# ModuleCarrier-Laird-BL652-v1_0_0.net
KiCad netlist of a schematic drawn in EAGLE
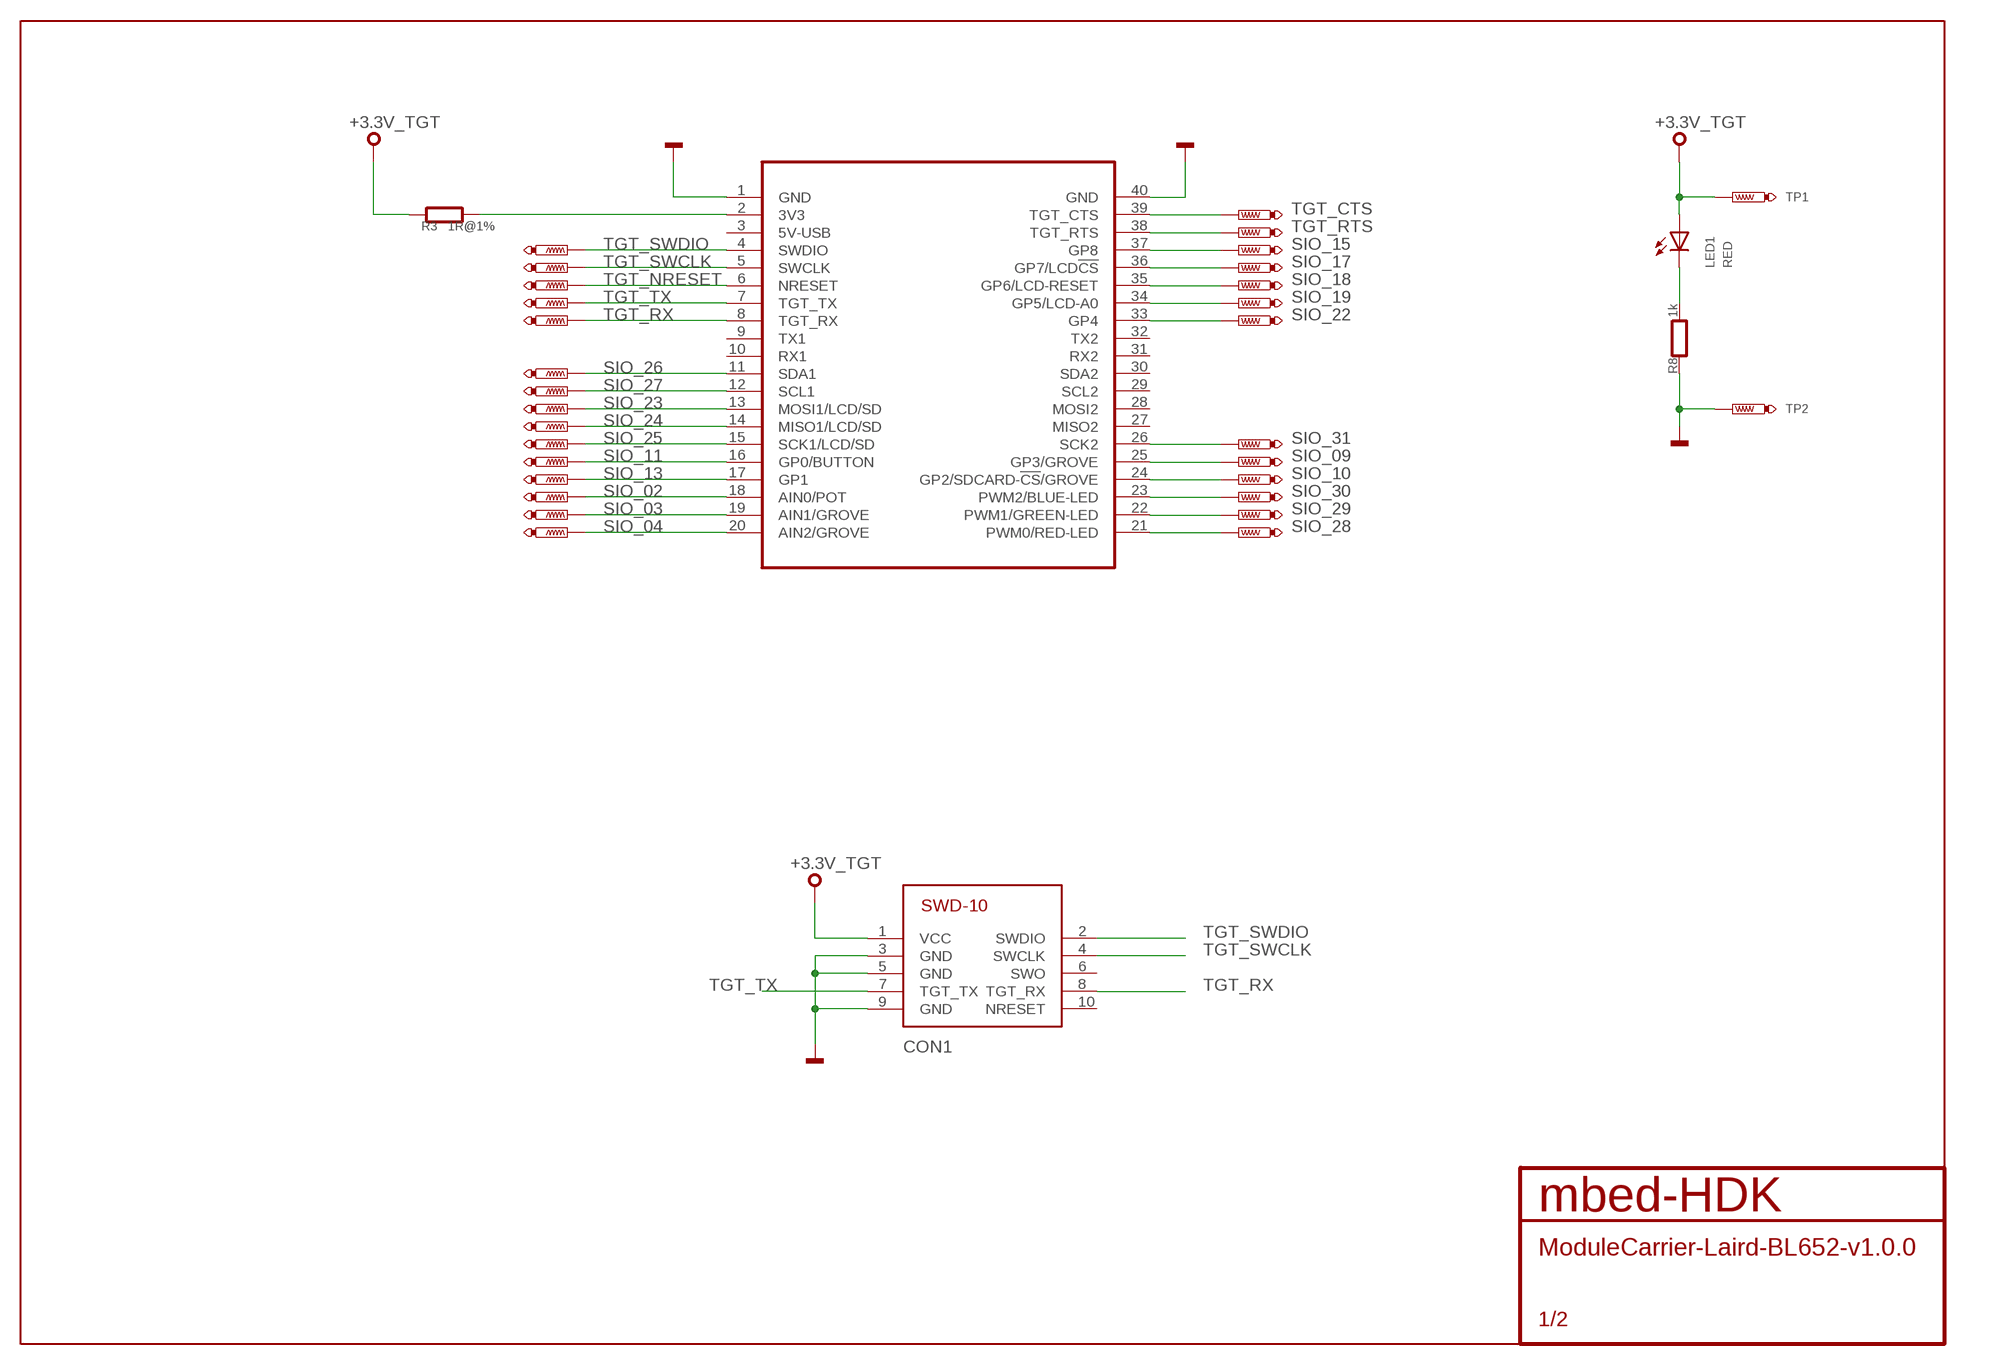
[diagram p0: schematic, sheet 1]
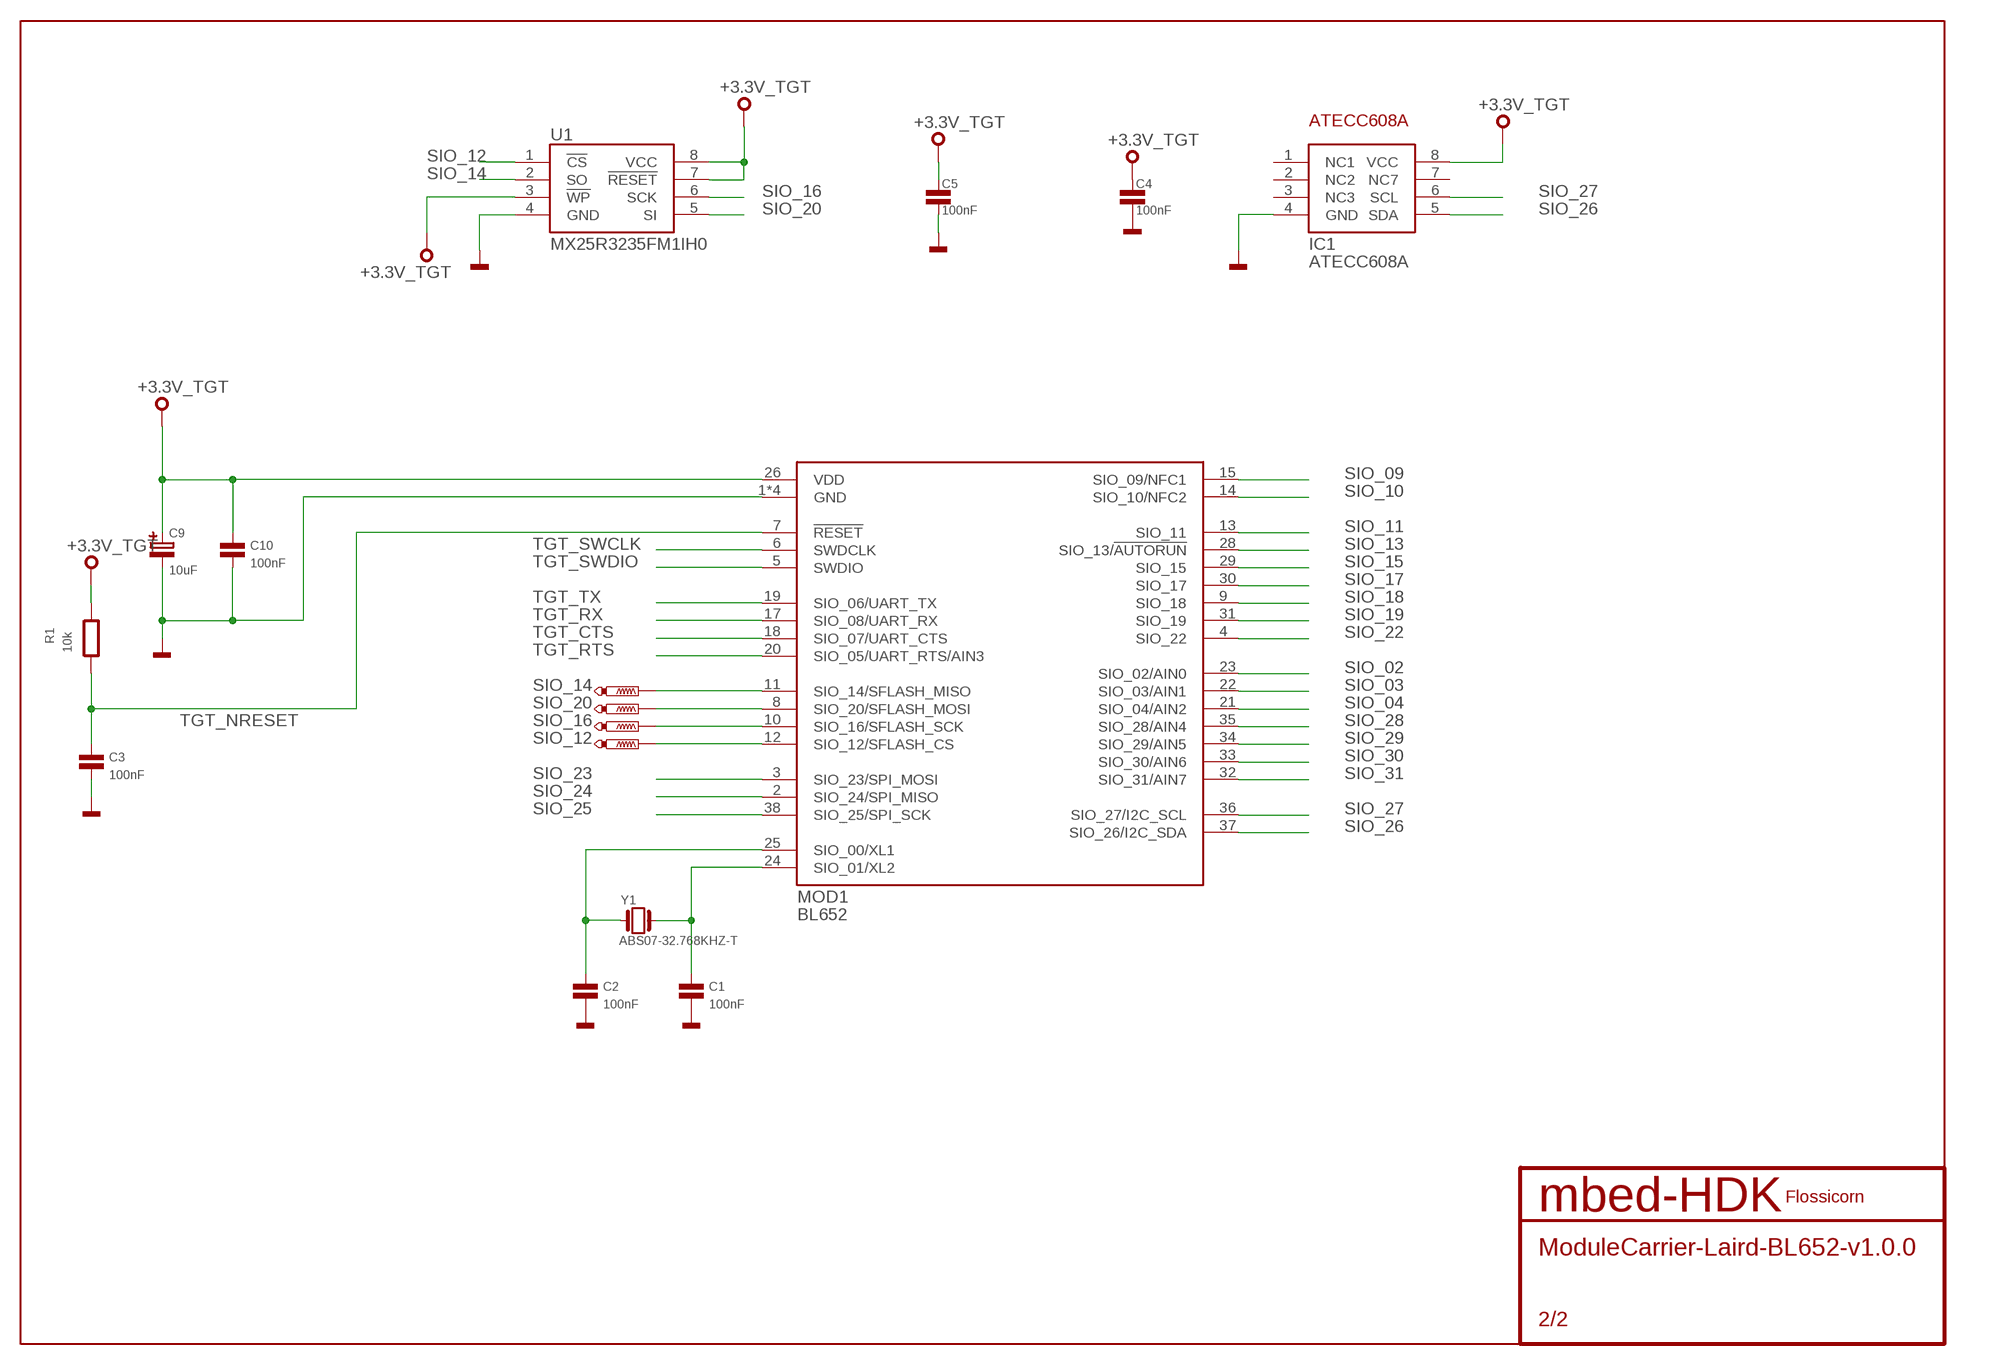
[diagram p1: schematic, sheet 2]

(export (version "E")
  (design (tool "Eeschema 10.0.6"))
  (components
    (comp (ref "C1")
      (value "100nF")
      (footprint "eagle-import:0603")
      (libsource (lib "eagle-import") (part "C0603"))
    )
    (comp (ref "C2")
      (value "100nF")
      (footprint "eagle-import:0603")
      (libsource (lib "eagle-import") (part "C0603"))
    )
    (comp (ref "C3")
      (value "100nF")
      (footprint "eagle-import:0603")
      (libsource (lib "eagle-import") (part "C0603"))
    )
    (comp (ref "C4")
      (value "100nF")
      (footprint "eagle-import:0603")
      (libsource (lib "eagle-import") (part "CAPACITOR0603"))
    )
    (comp (ref "C5")
      (value "100nF")
      (footprint "eagle-import:0603")
      (libsource (lib "eagle-import") (part "CAPACITOR0603"))
    )
    (comp (ref "C9")
      (value "10uF")
      (footprint "eagle-import:SMC_B")
      (fields (field (name "MF") "Kemet"))
      (libsource (lib "eagle-import") (part "CAPACITOR-POLARISEDB"))
    )
    (comp (ref "C10")
      (value "100nF")
      (footprint "eagle-import:0603")
      (libsource (lib "eagle-import") (part "C0603"))
    )
    (comp (ref "IC1")
      (value "ATECC608A")
      (footprint "eagle-import:SO8")
      (libsource (lib "eagle-import") (part "ATECC608A"))
    )
    (comp (ref "MOD1")
      (value "BL652")
      (footprint "eagle-import:BL652")
      (libsource (lib "eagle-import") (part "BL652"))
    )
    (comp (ref "R1")
      (value "10k")
      (footprint "eagle-import:0603")
      (libsource (lib "eagle-import") (part "RESISTOR0603"))
    )
    (comp (ref "SS1")
      (value "FLOSSICORN0.25")
      (footprint "eagle-import:FLOSSICORN-0.25")
      (libsource (lib "eagle-import") (part "FLOSSICORN0.25"))
    )
    (comp (ref "TP31")
      (value "PTR1TP07R")
      (footprint "eagle-import:TP07R")
      (libsource (lib "eagle-import") (part "PTR1TP07R"))
    )
    (comp (ref "TP32")
      (value "PTR1TP07R")
      (footprint "eagle-import:TP07R")
      (libsource (lib "eagle-import") (part "PTR1TP07R"))
    )
    (comp (ref "TP33")
      (value "PTR1TP07R")
      (footprint "eagle-import:TP07R")
      (libsource (lib "eagle-import") (part "PTR1TP07R"))
    )
    (comp (ref "TP34")
      (value "PTR1TP07R")
      (footprint "eagle-import:TP07R")
      (libsource (lib "eagle-import") (part "PTR1TP07R"))
    )
    (comp (ref "U1")
      (value "MX25R3235FM1IH0")
      (footprint "eagle-import:SO8")
      (fields (field (name "MF") "Macronix"))
      (libsource (lib "eagle-import") (part "MX25R3235FM1IH0"))
    )
    (comp (ref "Y1")
      (value "ABS07-32.768KHZ-T")
      (footprint "eagle-import:FC135")
      (fields (field (name "MF") "Abracon"))
      (libsource (lib "eagle-import") (part "ABS07-32.768KHZ-T"))
    )
    (comp (ref "CON1")
      (value "SWD-10/TC2050_SMD")
      (footprint "eagle-import:FTSH-105-02")
      (libsource (lib "eagle-import") (part "SWD-10/TC2050_SMD"))
    )
    (comp (ref "LED1")
      (value "RED")
      (footprint "eagle-import:CHIPLED_0603")
      (fields (field (name "MF") "Wurth Electronics Inc"))
      (libsource (lib "eagle-import") (part "SMD_LED0603"))
    )
    (comp (ref "MOD2")
      (value "MODULE_DAUGHTER")
      (footprint "eagle-import:MODULE_DAUGHTER")
      (libsource (lib "eagle-import") (part "MODULE_DAUGHTER"))
    )
    (comp (ref "R3")
      (value "1R@1%")
      (footprint "eagle-import:0603")
      (libsource (lib "eagle-import") (part "RESISTOR0603"))
    )
    (comp (ref "R8")
      (value "1k")
      (footprint "eagle-import:0603")
      (libsource (lib "eagle-import") (part "RESISTOR0603"))
    )
    (comp (ref "TP1")
      (value "TEST-POINT-50R-PTH")
      (footprint "eagle-import:TP50-PTH")
      (libsource (lib "eagle-import") (part "TEST-POINT-50R-PTH"))
    )
    (comp (ref "TP2")
      (value "TEST-POINT-50R-PTH")
      (footprint "eagle-import:TP50-PTH")
      (libsource (lib "eagle-import") (part "TEST-POINT-50R-PTH"))
    )
    (comp (ref "TP3")
      (value "PTR1TP07R")
      (footprint "eagle-import:TP07R")
      (libsource (lib "eagle-import") (part "PTR1TP07R"))
    )
    (comp (ref "TP4")
      (value "PTR1TP07R")
      (footprint "eagle-import:TP07R")
      (libsource (lib "eagle-import") (part "PTR1TP07R"))
    )
    (comp (ref "TP5")
      (value "PTR1TP07R")
      (footprint "eagle-import:TP07R")
      (libsource (lib "eagle-import") (part "PTR1TP07R"))
    )
    (comp (ref "TP6")
      (value "PTR1TP07R")
      (footprint "eagle-import:TP07R")
      (libsource (lib "eagle-import") (part "PTR1TP07R"))
    )
    (comp (ref "TP7")
      (value "PTR1TP07R")
      (footprint "eagle-import:TP07R")
      (libsource (lib "eagle-import") (part "PTR1TP07R"))
    )
    (comp (ref "TP8")
      (value "PTR1TP07R")
      (footprint "eagle-import:TP07R")
      (libsource (lib "eagle-import") (part "PTR1TP07R"))
    )
    (comp (ref "TP9")
      (value "PTR1TP07R")
      (footprint "eagle-import:TP07R")
      (libsource (lib "eagle-import") (part "PTR1TP07R"))
    )
    (comp (ref "TP10")
      (value "PTR1TP07R")
      (footprint "eagle-import:TP07R")
      (libsource (lib "eagle-import") (part "PTR1TP07R"))
    )
    (comp (ref "TP11")
      (value "PTR1TP07R")
      (footprint "eagle-import:TP07R")
      (libsource (lib "eagle-import") (part "PTR1TP07R"))
    )
    (comp (ref "TP12")
      (value "PTR1TP07R")
      (footprint "eagle-import:TP07R")
      (libsource (lib "eagle-import") (part "PTR1TP07R"))
    )
    (comp (ref "TP13")
      (value "PTR1TP07R")
      (footprint "eagle-import:TP07R")
      (libsource (lib "eagle-import") (part "PTR1TP07R"))
    )
    (comp (ref "TP14")
      (value "PTR1TP07R")
      (footprint "eagle-import:TP07R")
      (libsource (lib "eagle-import") (part "PTR1TP07R"))
    )
    (comp (ref "TP15")
      (value "PTR1TP07R")
      (footprint "eagle-import:TP07R")
      (libsource (lib "eagle-import") (part "PTR1TP07R"))
    )
    (comp (ref "TP16")
      (value "PTR1TP07R")
      (footprint "eagle-import:TP07R")
      (libsource (lib "eagle-import") (part "PTR1TP07R"))
    )
    (comp (ref "TP17")
      (value "PTR1TP07R")
      (footprint "eagle-import:TP07R")
      (libsource (lib "eagle-import") (part "PTR1TP07R"))
    )
    (comp (ref "TP18")
      (value "PTR1TP07R")
      (footprint "eagle-import:TP07R")
      (libsource (lib "eagle-import") (part "PTR1TP07R"))
    )
    (comp (ref "TP19")
      (value "PTR1TP07R")
      (footprint "eagle-import:TP07R")
      (libsource (lib "eagle-import") (part "PTR1TP07R"))
    )
    (comp (ref "TP20")
      (value "PTR1TP07R")
      (footprint "eagle-import:TP07R")
      (libsource (lib "eagle-import") (part "PTR1TP07R"))
    )
    (comp (ref "TP21")
      (value "PTR1TP07R")
      (footprint "eagle-import:TP07R")
      (libsource (lib "eagle-import") (part "PTR1TP07R"))
    )
    (comp (ref "TP22")
      (value "PTR1TP07R")
      (footprint "eagle-import:TP07R")
      (libsource (lib "eagle-import") (part "PTR1TP07R"))
    )
    (comp (ref "TP23")
      (value "PTR1TP07R")
      (footprint "eagle-import:TP07R")
      (libsource (lib "eagle-import") (part "PTR1TP07R"))
    )
    (comp (ref "TP24")
      (value "PTR1TP07R")
      (footprint "eagle-import:TP07R")
      (libsource (lib "eagle-import") (part "PTR1TP07R"))
    )
    (comp (ref "TP25")
      (value "PTR1TP07R")
      (footprint "eagle-import:TP07R")
      (libsource (lib "eagle-import") (part "PTR1TP07R"))
    )
    (comp (ref "TP26")
      (value "PTR1TP07R")
      (footprint "eagle-import:TP07R")
      (libsource (lib "eagle-import") (part "PTR1TP07R"))
    )
    (comp (ref "TP27")
      (value "PTR1TP07R")
      (footprint "eagle-import:TP07R")
      (libsource (lib "eagle-import") (part "PTR1TP07R"))
    )
    (comp (ref "TP28")
      (value "PTR1TP07R")
      (footprint "eagle-import:TP07R")
      (libsource (lib "eagle-import") (part "PTR1TP07R"))
    )
    (comp (ref "TP29")
      (value "PTR1TP07R")
      (footprint "eagle-import:TP07R")
      (libsource (lib "eagle-import") (part "PTR1TP07R"))
    )
    (comp (ref "TP30")
      (value "PTR1TP07R")
      (footprint "eagle-import:TP07R")
      (libsource (lib "eagle-import") (part "PTR1TP07R"))
    )
  )
  (nets
    (net (code "1") (name "+3.3V_TGT") (class "Default")
      (node (ref "C10") (pin "1") (pinfunction "P$1_1") (pintype "passive"))
      (node (ref "C4") (pin "1") (pinfunction "P$1_1") (pintype "passive"))
      (node (ref "C5") (pin "1") (pinfunction "P$1_1") (pintype "passive"))
      (node (ref "C9") (pin "+") (pinfunction "+_+") (pintype "passive"))
      (node (ref "CON1") (pin "1") (pinfunction "VCC_1") (pintype "bidirectional"))
      (node (ref "IC1") (pin "8") (pinfunction "VCC_8") (pintype "bidirectional"))
      (node (ref "LED1") (pin "A") (pinfunction "A_A") (pintype "passive"))
      (node (ref "MOD1") (pin "26") (pinfunction "VDD_26") (pintype "bidirectional"))
      (node (ref "R1") (pin "2") (pinfunction "P$2_2") (pintype "passive"))
      (node (ref "R3") (pin "1") (pinfunction "P$1_1") (pintype "passive"))
      (node (ref "TP1") (pin "TP") (pinfunction "TP_TP") (pintype "input"))
      (node (ref "U1") (pin "3") (pinfunction "~{WP}_3") (pintype "bidirectional"))
      (node (ref "U1") (pin "7") (pinfunction "~{RESET}_7") (pintype "bidirectional"))
      (node (ref "U1") (pin "8") (pinfunction "VCC_8") (pintype "bidirectional"))
    )
    (net (code "2") (name "GND") (class "Default")
      (node (ref "C1") (pin "2") (pinfunction "P$2_2") (pintype "passive"))
      (node (ref "C10") (pin "2") (pinfunction "P$2_2") (pintype "passive"))
      (node (ref "C2") (pin "2") (pinfunction "P$2_2") (pintype "passive"))
      (node (ref "C3") (pin "2") (pinfunction "P$2_2") (pintype "passive"))
      (node (ref "C4") (pin "2") (pinfunction "P$2_2") (pintype "passive"))
      (node (ref "C5") (pin "2") (pinfunction "P$2_2") (pintype "passive"))
      (node (ref "C9") (pin "-") (pinfunction "-_-") (pintype "passive"))
      (node (ref "CON1") (pin "3") (pinfunction "GND_3") (pintype "bidirectional"))
      (node (ref "CON1") (pin "5") (pinfunction "GND_5") (pintype "bidirectional"))
      (node (ref "CON1") (pin "9") (pinfunction "GND_9") (pintype "bidirectional"))
      (node (ref "IC1") (pin "4") (pinfunction "GND_4") (pintype "bidirectional"))
      (node (ref "MOD1") (pin "1") (pinfunction "GND_1") (pintype "bidirectional"))
      (node (ref "MOD1") (pin "16") (pinfunction "GND_16") (pintype "bidirectional"))
      (node (ref "MOD1") (pin "27") (pinfunction "GND_27") (pintype "bidirectional"))
      (node (ref "MOD1") (pin "39") (pinfunction "GND_39") (pintype "bidirectional"))
      (node (ref "MOD2") (pin "1") (pinfunction "GND_1") (pintype "bidirectional"))
      (node (ref "MOD2") (pin "40") (pinfunction "GND_40") (pintype "bidirectional"))
      (node (ref "R8") (pin "1") (pinfunction "P$1_1") (pintype "passive"))
      (node (ref "TP2") (pin "TP") (pinfunction "TP_TP") (pintype "input"))
      (node (ref "U1") (pin "4") (pinfunction "GND_4") (pintype "bidirectional"))
    )
    (net (code "3") (name "Net-(C1-P$1)") (class "Default")
      (node (ref "C1") (pin "1") (pinfunction "P$1_1") (pintype "passive"))
      (node (ref "MOD1") (pin "24") (pinfunction "SIO_01/XL2_24") (pintype "bidirectional"))
      (node (ref "Y1") (pin "X2") (pinfunction "2_X2") (pintype "passive"))
    )
    (net (code "4") (name "Net-(C2-P$1)") (class "Default")
      (node (ref "C2") (pin "1") (pinfunction "P$1_1") (pintype "passive"))
      (node (ref "MOD1") (pin "25") (pinfunction "SIO_00/XL1_25") (pintype "bidirectional"))
      (node (ref "Y1") (pin "X1") (pinfunction "1_X1") (pintype "passive"))
    )
    (net (code "5") (name "Net-(MOD2-3V3)") (class "Default")
      (node (ref "MOD2") (pin "2") (pinfunction "3V3_2") (pintype "bidirectional"))
      (node (ref "R3") (pin "2") (pinfunction "P$2_2") (pintype "passive"))
    )
    (net (code "6") (name "Net-(R8-P$2)") (class "Default")
      (node (ref "LED1") (pin "C") (pinfunction "C_C") (pintype "passive"))
      (node (ref "R8") (pin "2") (pinfunction "P$2_2") (pintype "passive"))
    )
    (net (code "7") (name "SIO_02") (class "Default")
      (node (ref "MOD1") (pin "23") (pinfunction "SIO_02/AIN0_23") (pintype "bidirectional"))
      (node (ref "MOD2") (pin "18") (pinfunction "AIN0/POT_18") (pintype "bidirectional"))
      (node (ref "TP10") (pin "TP") (pinfunction "TP_TP") (pintype "input"))
    )
    (net (code "8") (name "SIO_03") (class "Default")
      (node (ref "MOD1") (pin "22") (pinfunction "SIO_03/AIN1_22") (pintype "bidirectional"))
      (node (ref "MOD2") (pin "19") (pinfunction "AIN1/GROVE_19") (pintype "bidirectional"))
      (node (ref "TP11") (pin "TP") (pinfunction "TP_TP") (pintype "input"))
    )
    (net (code "9") (name "SIO_04") (class "Default")
      (node (ref "MOD1") (pin "21") (pinfunction "SIO_04/AIN2_21") (pintype "bidirectional"))
      (node (ref "MOD2") (pin "20") (pinfunction "AIN2/GROVE_20") (pintype "bidirectional"))
      (node (ref "TP12") (pin "TP") (pinfunction "TP_TP") (pintype "input"))
    )
    (net (code "10") (name "SIO_09") (class "Default")
      (node (ref "MOD1") (pin "15") (pinfunction "SIO_09/NFC1_15") (pintype "bidirectional"))
      (node (ref "MOD2") (pin "25") (pinfunction "GP3/GROVE_25") (pintype "bidirectional"))
      (node (ref "TP17") (pin "TP") (pinfunction "TP_TP") (pintype "input"))
    )
    (net (code "11") (name "SIO_10") (class "Default")
      (node (ref "MOD1") (pin "14") (pinfunction "SIO_10/NFC2_14") (pintype "bidirectional"))
      (node (ref "MOD2") (pin "24") (pinfunction "GP2/SDCARD-~{CS}/GROVE_24") (pintype "bidirectional"))
      (node (ref "TP16") (pin "TP") (pinfunction "TP_TP") (pintype "input"))
    )
    (net (code "12") (name "SIO_11") (class "Default")
      (node (ref "MOD1") (pin "13") (pinfunction "SIO_11_13") (pintype "bidirectional"))
      (node (ref "MOD2") (pin "16") (pinfunction "GP0/BUTTON_16") (pintype "bidirectional"))
      (node (ref "TP8") (pin "TP") (pinfunction "TP_TP") (pintype "input"))
    )
    (net (code "13") (name "SIO_12") (class "Default")
      (node (ref "MOD1") (pin "12") (pinfunction "SIO_12/SFLASH_CS_12") (pintype "bidirectional"))
      (node (ref "TP34") (pin "TP") (pinfunction "TP_TP") (pintype "input"))
      (node (ref "U1") (pin "1") (pinfunction "~{CS}_1") (pintype "bidirectional"))
    )
    (net (code "14") (name "SIO_13") (class "Default")
      (node (ref "MOD1") (pin "28") (pinfunction "SIO_13/~{AUTORUN}_28") (pintype "bidirectional"))
      (node (ref "MOD2") (pin "17") (pinfunction "GP1_17") (pintype "bidirectional"))
      (node (ref "TP9") (pin "TP") (pinfunction "TP_TP") (pintype "input"))
    )
    (net (code "15") (name "SIO_14") (class "Default")
      (node (ref "MOD1") (pin "11") (pinfunction "SIO_14/SFLASH_MISO_11") (pintype "bidirectional"))
      (node (ref "TP31") (pin "TP") (pinfunction "TP_TP") (pintype "input"))
      (node (ref "U1") (pin "2") (pinfunction "SO_2") (pintype "bidirectional"))
    )
    (net (code "16") (name "SIO_15") (class "Default")
      (node (ref "MOD1") (pin "29") (pinfunction "SIO_15_29") (pintype "bidirectional"))
      (node (ref "MOD2") (pin "37") (pinfunction "GP8_37") (pintype "bidirectional"))
      (node (ref "TP22") (pin "TP") (pinfunction "TP_TP") (pintype "input"))
    )
    (net (code "17") (name "SIO_16") (class "Default")
      (node (ref "MOD1") (pin "10") (pinfunction "SIO_16/SFLASH_SCK_10") (pintype "bidirectional"))
      (node (ref "TP33") (pin "TP") (pinfunction "TP_TP") (pintype "input"))
      (node (ref "U1") (pin "6") (pinfunction "SCK_6") (pintype "bidirectional"))
    )
    (net (code "18") (name "SIO_17") (class "Default")
      (node (ref "MOD1") (pin "30") (pinfunction "SIO_17_30") (pintype "bidirectional"))
      (node (ref "MOD2") (pin "36") (pinfunction "GP7/LCD~{CS}_36") (pintype "bidirectional"))
      (node (ref "TP21") (pin "TP") (pinfunction "TP_TP") (pintype "input"))
    )
    (net (code "19") (name "SIO_18") (class "Default")
      (node (ref "MOD1") (pin "9") (pinfunction "SIO_18_9") (pintype "bidirectional"))
      (node (ref "MOD2") (pin "35") (pinfunction "GP6/LCD-RESET_35") (pintype "bidirectional"))
      (node (ref "TP20") (pin "TP") (pinfunction "TP_TP") (pintype "input"))
    )
    (net (code "20") (name "SIO_19") (class "Default")
      (node (ref "MOD1") (pin "31") (pinfunction "SIO_19_31") (pintype "bidirectional"))
      (node (ref "MOD2") (pin "34") (pinfunction "GP5/LCD-A0_34") (pintype "bidirectional"))
      (node (ref "TP19") (pin "TP") (pinfunction "TP_TP") (pintype "input"))
    )
    (net (code "21") (name "SIO_20") (class "Default")
      (node (ref "MOD1") (pin "8") (pinfunction "SIO_20/SFLASH_MOSI_8") (pintype "bidirectional"))
      (node (ref "TP32") (pin "TP") (pinfunction "TP_TP") (pintype "input"))
      (node (ref "U1") (pin "5") (pinfunction "SI_5") (pintype "bidirectional"))
    )
    (net (code "22") (name "SIO_22") (class "Default")
      (node (ref "MOD1") (pin "4") (pinfunction "SIO_22_4") (pintype "bidirectional"))
      (node (ref "MOD2") (pin "33") (pinfunction "GP4_33") (pintype "bidirectional"))
      (node (ref "TP18") (pin "TP") (pinfunction "TP_TP") (pintype "input"))
    )
    (net (code "23") (name "SIO_23") (class "Default")
      (node (ref "MOD1") (pin "3") (pinfunction "SIO_23/SPI_MOSI_3") (pintype "bidirectional"))
      (node (ref "MOD2") (pin "13") (pinfunction "MOSI1/LCD/SD_13") (pintype "bidirectional"))
      (node (ref "TP5") (pin "TP") (pinfunction "TP_TP") (pintype "input"))
    )
    (net (code "24") (name "SIO_24") (class "Default")
      (node (ref "MOD1") (pin "2") (pinfunction "SIO_24/SPI_MISO_2") (pintype "bidirectional"))
      (node (ref "MOD2") (pin "14") (pinfunction "MISO1/LCD/SD_14") (pintype "bidirectional"))
      (node (ref "TP6") (pin "TP") (pinfunction "TP_TP") (pintype "input"))
    )
    (net (code "25") (name "SIO_25") (class "Default")
      (node (ref "MOD1") (pin "38") (pinfunction "SIO_25/SPI_SCK_38") (pintype "bidirectional"))
      (node (ref "MOD2") (pin "15") (pinfunction "SCK1/LCD/SD_15") (pintype "bidirectional"))
      (node (ref "TP7") (pin "TP") (pinfunction "TP_TP") (pintype "input"))
    )
    (net (code "26") (name "SIO_26") (class "Default")
      (node (ref "IC1") (pin "5") (pinfunction "SDA_5") (pintype "bidirectional"))
      (node (ref "MOD1") (pin "37") (pinfunction "SIO_26/I2C_SDA_37") (pintype "bidirectional"))
      (node (ref "MOD2") (pin "11") (pinfunction "SDA1_11") (pintype "bidirectional"))
      (node (ref "TP3") (pin "TP") (pinfunction "TP_TP") (pintype "input"))
    )
    (net (code "27") (name "SIO_27") (class "Default")
      (node (ref "IC1") (pin "6") (pinfunction "SCL_6") (pintype "bidirectional"))
      (node (ref "MOD1") (pin "36") (pinfunction "SIO_27/I2C_SCL_36") (pintype "bidirectional"))
      (node (ref "MOD2") (pin "12") (pinfunction "SCL1_12") (pintype "bidirectional"))
      (node (ref "TP4") (pin "TP") (pinfunction "TP_TP") (pintype "input"))
    )
    (net (code "28") (name "SIO_28") (class "Default")
      (node (ref "MOD1") (pin "35") (pinfunction "SIO_28/AIN4_35") (pintype "bidirectional"))
      (node (ref "MOD2") (pin "21") (pinfunction "PWM0/RED-LED_21") (pintype "bidirectional"))
      (node (ref "TP13") (pin "TP") (pinfunction "TP_TP") (pintype "input"))
    )
    (net (code "29") (name "SIO_29") (class "Default")
      (node (ref "MOD1") (pin "34") (pinfunction "SIO_29/AIN5_34") (pintype "bidirectional"))
      (node (ref "MOD2") (pin "22") (pinfunction "PWM1/GREEN-LED_22") (pintype "bidirectional"))
      (node (ref "TP14") (pin "TP") (pinfunction "TP_TP") (pintype "input"))
    )
    (net (code "30") (name "SIO_30") (class "Default")
      (node (ref "MOD1") (pin "33") (pinfunction "SIO_30/AIN6_33") (pintype "bidirectional"))
      (node (ref "MOD2") (pin "23") (pinfunction "PWM2/BLUE-LED_23") (pintype "bidirectional"))
      (node (ref "TP15") (pin "TP") (pinfunction "TP_TP") (pintype "input"))
    )
    (net (code "31") (name "SIO_31") (class "Default")
      (node (ref "MOD1") (pin "32") (pinfunction "SIO_31/AIN7_32") (pintype "bidirectional"))
      (node (ref "MOD2") (pin "26") (pinfunction "SCK2_26") (pintype "bidirectional"))
      (node (ref "TP25") (pin "TP") (pinfunction "TP_TP") (pintype "input"))
    )
    (net (code "32") (name "TGT_CTS") (class "Default")
      (node (ref "MOD1") (pin "18") (pinfunction "SIO_07/UART_CTS_18") (pintype "bidirectional"))
      (node (ref "MOD2") (pin "39") (pinfunction "TGT_CTS_39") (pintype "bidirectional"))
      (node (ref "TP24") (pin "TP") (pinfunction "TP_TP") (pintype "input"))
    )
    (net (code "33") (name "TGT_NRESET") (class "Default")
      (node (ref "C3") (pin "1") (pinfunction "P$1_1") (pintype "passive"))
      (node (ref "MOD1") (pin "7") (pinfunction "~{RESET}_7") (pintype "bidirectional"))
      (node (ref "MOD2") (pin "6") (pinfunction "NRESET_6") (pintype "bidirectional"))
      (node (ref "R1") (pin "1") (pinfunction "P$1_1") (pintype "passive"))
      (node (ref "TP28") (pin "TP") (pinfunction "TP_TP") (pintype "input"))
    )
    (net (code "34") (name "TGT_RTS") (class "Default")
      (node (ref "MOD1") (pin "20") (pinfunction "SIO_05/UART_RTS/AIN3_20") (pintype "bidirectional"))
      (node (ref "MOD2") (pin "38") (pinfunction "TGT_RTS_38") (pintype "bidirectional"))
      (node (ref "TP23") (pin "TP") (pinfunction "TP_TP") (pintype "input"))
    )
    (net (code "35") (name "TGT_RX") (class "Default")
      (node (ref "CON1") (pin "8") (pinfunction "TGT_RX_8") (pintype "bidirectional"))
      (node (ref "MOD1") (pin "17") (pinfunction "SIO_08/UART_RX_17") (pintype "bidirectional"))
      (node (ref "MOD2") (pin "8") (pinfunction "TGT_RX_8") (pintype "bidirectional"))
      (node (ref "TP30") (pin "TP") (pinfunction "TP_TP") (pintype "input"))
    )
    (net (code "36") (name "TGT_SWCLK") (class "Default")
      (node (ref "CON1") (pin "4") (pinfunction "SWCLK_4") (pintype "bidirectional"))
      (node (ref "MOD1") (pin "6") (pinfunction "SWDCLK_6") (pintype "bidirectional"))
      (node (ref "MOD2") (pin "5") (pinfunction "SWCLK_5") (pintype "bidirectional"))
      (node (ref "TP27") (pin "TP") (pinfunction "TP_TP") (pintype "input"))
    )
    (net (code "37") (name "TGT_SWDIO") (class "Default")
      (node (ref "CON1") (pin "2") (pinfunction "SWDIO_2") (pintype "bidirectional"))
      (node (ref "MOD1") (pin "5") (pinfunction "SWDIO_5") (pintype "bidirectional"))
      (node (ref "MOD2") (pin "4") (pinfunction "SWDIO_4") (pintype "bidirectional"))
      (node (ref "TP26") (pin "TP") (pinfunction "TP_TP") (pintype "input"))
    )
    (net (code "38") (name "TGT_TX") (class "Default")
      (node (ref "CON1") (pin "7") (pinfunction "TGT_TX_7") (pintype "bidirectional"))
      (node (ref "MOD1") (pin "19") (pinfunction "SIO_06/UART_TX_19") (pintype "bidirectional"))
      (node (ref "MOD2") (pin "7") (pinfunction "TGT_TX_7") (pintype "bidirectional"))
      (node (ref "TP29") (pin "TP") (pinfunction "TP_TP") (pintype "input"))
    )
    (net (code "39") (name "unconnected-(CON1-NRESET-Pad10)") (class "Default")
      (node (ref "CON1") (pin "10") (pinfunction "NRESET_10") (pintype "bidirectional"))
    )
    (net (code "40") (name "unconnected-(CON1-SWO-Pad6)") (class "Default")
      (node (ref "CON1") (pin "6") (pinfunction "SWO_6") (pintype "bidirectional"))
    )
    (net (code "41") (name "unconnected-(IC1-NC1-Pad1)") (class "Default")
      (node (ref "IC1") (pin "1") (pinfunction "NC1_1") (pintype "bidirectional"))
    )
    (net (code "42") (name "unconnected-(IC1-NC2-Pad2)") (class "Default")
      (node (ref "IC1") (pin "2") (pinfunction "NC2_2") (pintype "bidirectional"))
    )
    (net (code "43") (name "unconnected-(IC1-NC3-Pad3)") (class "Default")
      (node (ref "IC1") (pin "3") (pinfunction "NC3_3") (pintype "bidirectional"))
    )
    (net (code "44") (name "unconnected-(IC1-NC7-Pad7)") (class "Default")
      (node (ref "IC1") (pin "7") (pinfunction "NC7_7") (pintype "bidirectional"))
    )
    (net (code "45") (name "unconnected-(MOD2-5V-USB-Pad3)") (class "Default")
      (node (ref "MOD2") (pin "3") (pinfunction "5V-USB_3") (pintype "bidirectional"))
    )
    (net (code "46") (name "unconnected-(MOD2-MISO2-Pad27)") (class "Default")
      (node (ref "MOD2") (pin "27") (pinfunction "MISO2_27") (pintype "bidirectional"))
    )
    (net (code "47") (name "unconnected-(MOD2-MOSI2-Pad28)") (class "Default")
      (node (ref "MOD2") (pin "28") (pinfunction "MOSI2_28") (pintype "bidirectional"))
    )
    (net (code "48") (name "unconnected-(MOD2-RX1-Pad10)") (class "Default")
      (node (ref "MOD2") (pin "10") (pinfunction "RX1_10") (pintype "bidirectional"))
    )
    (net (code "49") (name "unconnected-(MOD2-RX2-Pad31)") (class "Default")
      (node (ref "MOD2") (pin "31") (pinfunction "RX2_31") (pintype "bidirectional"))
    )
    (net (code "50") (name "unconnected-(MOD2-SCL2-Pad29)") (class "Default")
      (node (ref "MOD2") (pin "29") (pinfunction "SCL2_29") (pintype "bidirectional"))
    )
    (net (code "51") (name "unconnected-(MOD2-SDA2-Pad30)") (class "Default")
      (node (ref "MOD2") (pin "30") (pinfunction "SDA2_30") (pintype "bidirectional"))
    )
    (net (code "52") (name "unconnected-(MOD2-TX1-Pad9)") (class "Default")
      (node (ref "MOD2") (pin "9") (pinfunction "TX1_9") (pintype "bidirectional"))
    )
    (net (code "53") (name "unconnected-(MOD2-TX2-Pad32)") (class "Default")
      (node (ref "MOD2") (pin "32") (pinfunction "TX2_32") (pintype "bidirectional"))
    )
  )
)
